# piezo-buffer-and-preamp-ritter_V0-2alt.net
KiCad netlist of a schematic drawn in EAGLE
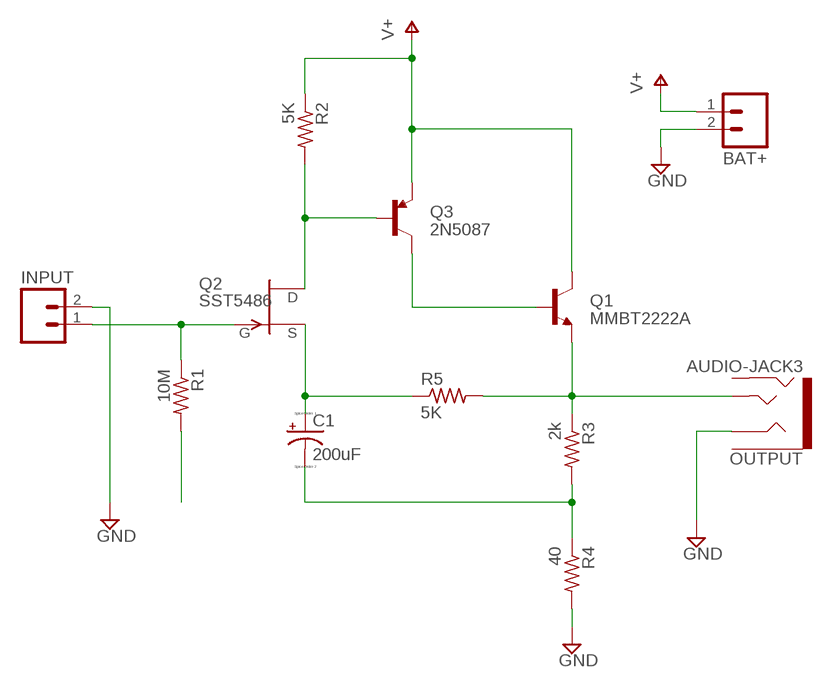
[diagram p0: schematic, sheet 1]

(export (version "E")
  (design (tool "Eeschema 10.0.6"))
  (components
    (comp (ref "BAT+")
      (value "M02LOCK")
      (footprint "eagle-import:1X02_LOCK")
      (libsource (lib "eagle-import") (part "M02LOCK"))
    )
    (comp (ref "C1")
      (value "200uF")
      (footprint "eagle-import:153CLV-0810")
      (libsource (lib "eagle-import") (part "CPOL-US153CLV-0810"))
    )
    (comp (ref "INPUT")
      (value "M02LOCK")
      (footprint "eagle-import:1X02_LOCK")
      (libsource (lib "eagle-import") (part "M02LOCK"))
    )
    (comp (ref "OUTPUT")
      (value "AUDIO-JACK3")
      (footprint "eagle-import:AUDIO-JACK-TRRS-SMD")
      (libsource (lib "eagle-import") (part "AUDIO-JACK3"))
    )
    (comp (ref "Q1")
      (value "MMBT2222A")
      (footprint "eagle-import:SOT23")
      (libsource (lib "eagle-import") (part "TRANSISTOR_NPN"))
    )
    (comp (ref "Q2")
      (value "SST5486")
      (footprint "eagle-import:SOT23")
      (libsource (lib "eagle-import") (part "?548SST6"))
    )
    (comp (ref "Q3")
      (value "2N5087")
      (footprint "eagle-import:SOT23")
      (libsource (lib "eagle-import") (part "TRANSISTOR_PNP"))
    )
    (comp (ref "R1")
      (value "10M")
      (footprint "eagle-import:R0805")
      (libsource (lib "eagle-import") (part "R-US_R0805"))
    )
    (comp (ref "R2")
      (value "5K")
      (footprint "eagle-import:R0805")
      (libsource (lib "eagle-import") (part "R-US_R0805"))
    )
    (comp (ref "R3")
      (value "2k")
      (footprint "eagle-import:R0805")
      (libsource (lib "eagle-import") (part "R-US_R0805"))
    )
    (comp (ref "R4")
      (value "40")
      (footprint "eagle-import:R0805")
      (libsource (lib "eagle-import") (part "R-US_R0805"))
    )
    (comp (ref "R5")
      (value "5K")
      (footprint "eagle-import:R0805")
      (libsource (lib "eagle-import") (part "R-US_R0805"))
    )
  )
  (nets
    (net (code "1") (name "GND") (class "Default")
      (node (ref "BAT+") (pin "2") (pinfunction "2_2") (pintype "passive"))
      (node (ref "INPUT") (pin "2") (pinfunction "2_2") (pintype "passive"))
      (node (ref "OUTPUT") (pin "RING1") (pinfunction "RING1_RING1") (pintype "bidirectional"))
      (node (ref "R4") (pin "2") (pinfunction "2_2") (pintype "passive"))
    )
    (net (code "2") (name "Net-(C1-Pad-)") (class "Default")
      (node (ref "C1") (pin "-") (pinfunction "-_-") (pintype "passive"))
      (node (ref "R3") (pin "2") (pinfunction "2_2") (pintype "passive"))
      (node (ref "R4") (pin "1") (pinfunction "1_1") (pintype "passive"))
    )
    (net (code "3") (name "Net-(Q1-B)") (class "Default")
      (node (ref "Q1") (pin "1") (pinfunction "B_1") (pintype "passive"))
      (node (ref "Q3") (pin "3") (pinfunction "C_3") (pintype "passive"))
    )
    (net (code "4") (name "Net-(Q1-E)") (class "Default")
      (node (ref "OUTPUT") (pin "TIP") (pinfunction "TIP_TIP") (pintype "bidirectional"))
      (node (ref "Q1") (pin "2") (pinfunction "E_2") (pintype "passive"))
      (node (ref "R3") (pin "1") (pinfunction "1_1") (pintype "passive"))
      (node (ref "R5") (pin "2") (pinfunction "2_2") (pintype "passive"))
    )
    (net (code "5") (name "Net-(Q2-D)") (class "Default")
      (node (ref "Q2") (pin "1") (pinfunction "D_1") (pintype "passive"))
      (node (ref "Q3") (pin "1") (pinfunction "B_1") (pintype "passive"))
      (node (ref "R2") (pin "2") (pinfunction "2_2") (pintype "passive"))
    )
    (net (code "6") (name "Net-(Q2-G)") (class "Default")
      (node (ref "INPUT") (pin "1") (pinfunction "1_1") (pintype "passive"))
      (node (ref "Q2") (pin "3") (pinfunction "G_3") (pintype "passive"))
      (node (ref "R1") (pin "1") (pinfunction "1_1") (pintype "passive"))
    )
    (net (code "7") (name "Net-(Q2-S)") (class "Default")
      (node (ref "C1") (pin "+") (pinfunction "+_+") (pintype "passive"))
      (node (ref "Q2") (pin "2") (pinfunction "S_2") (pintype "passive"))
      (node (ref "R5") (pin "1") (pinfunction "1_1") (pintype "passive"))
    )
    (net (code "8") (name "V+") (class "Default")
      (node (ref "BAT+") (pin "1") (pinfunction "1_1") (pintype "passive"))
      (node (ref "Q1") (pin "3") (pinfunction "C_3") (pintype "passive"))
      (node (ref "Q3") (pin "2") (pinfunction "E_2") (pintype "passive"))
      (node (ref "R2") (pin "1") (pinfunction "1_1") (pintype "passive"))
    )
    (net (code "9") (name "unconnected-(OUTPUT-PadEARTH)") (class "Default")
      (node (ref "OUTPUT") (pin "EARTH") (pinfunction "EARTH_EARTH") (pintype "bidirectional"))
    )
    (net (code "10") (name "unconnected-(OUTPUT-PadRING2)") (class "Default")
      (node (ref "OUTPUT") (pin "RING2") (pinfunction "RING2_RING2") (pintype "bidirectional"))
    )
    (net (code "11") (name "unconnected-(R1-Pad2)") (class "Default")
      (node (ref "R1") (pin "2") (pinfunction "2_2") (pintype "passive"))
    )
  )
)
